# SparkFun_AVR_Stick.net
KiCad netlist of a schematic drawn in EAGLE
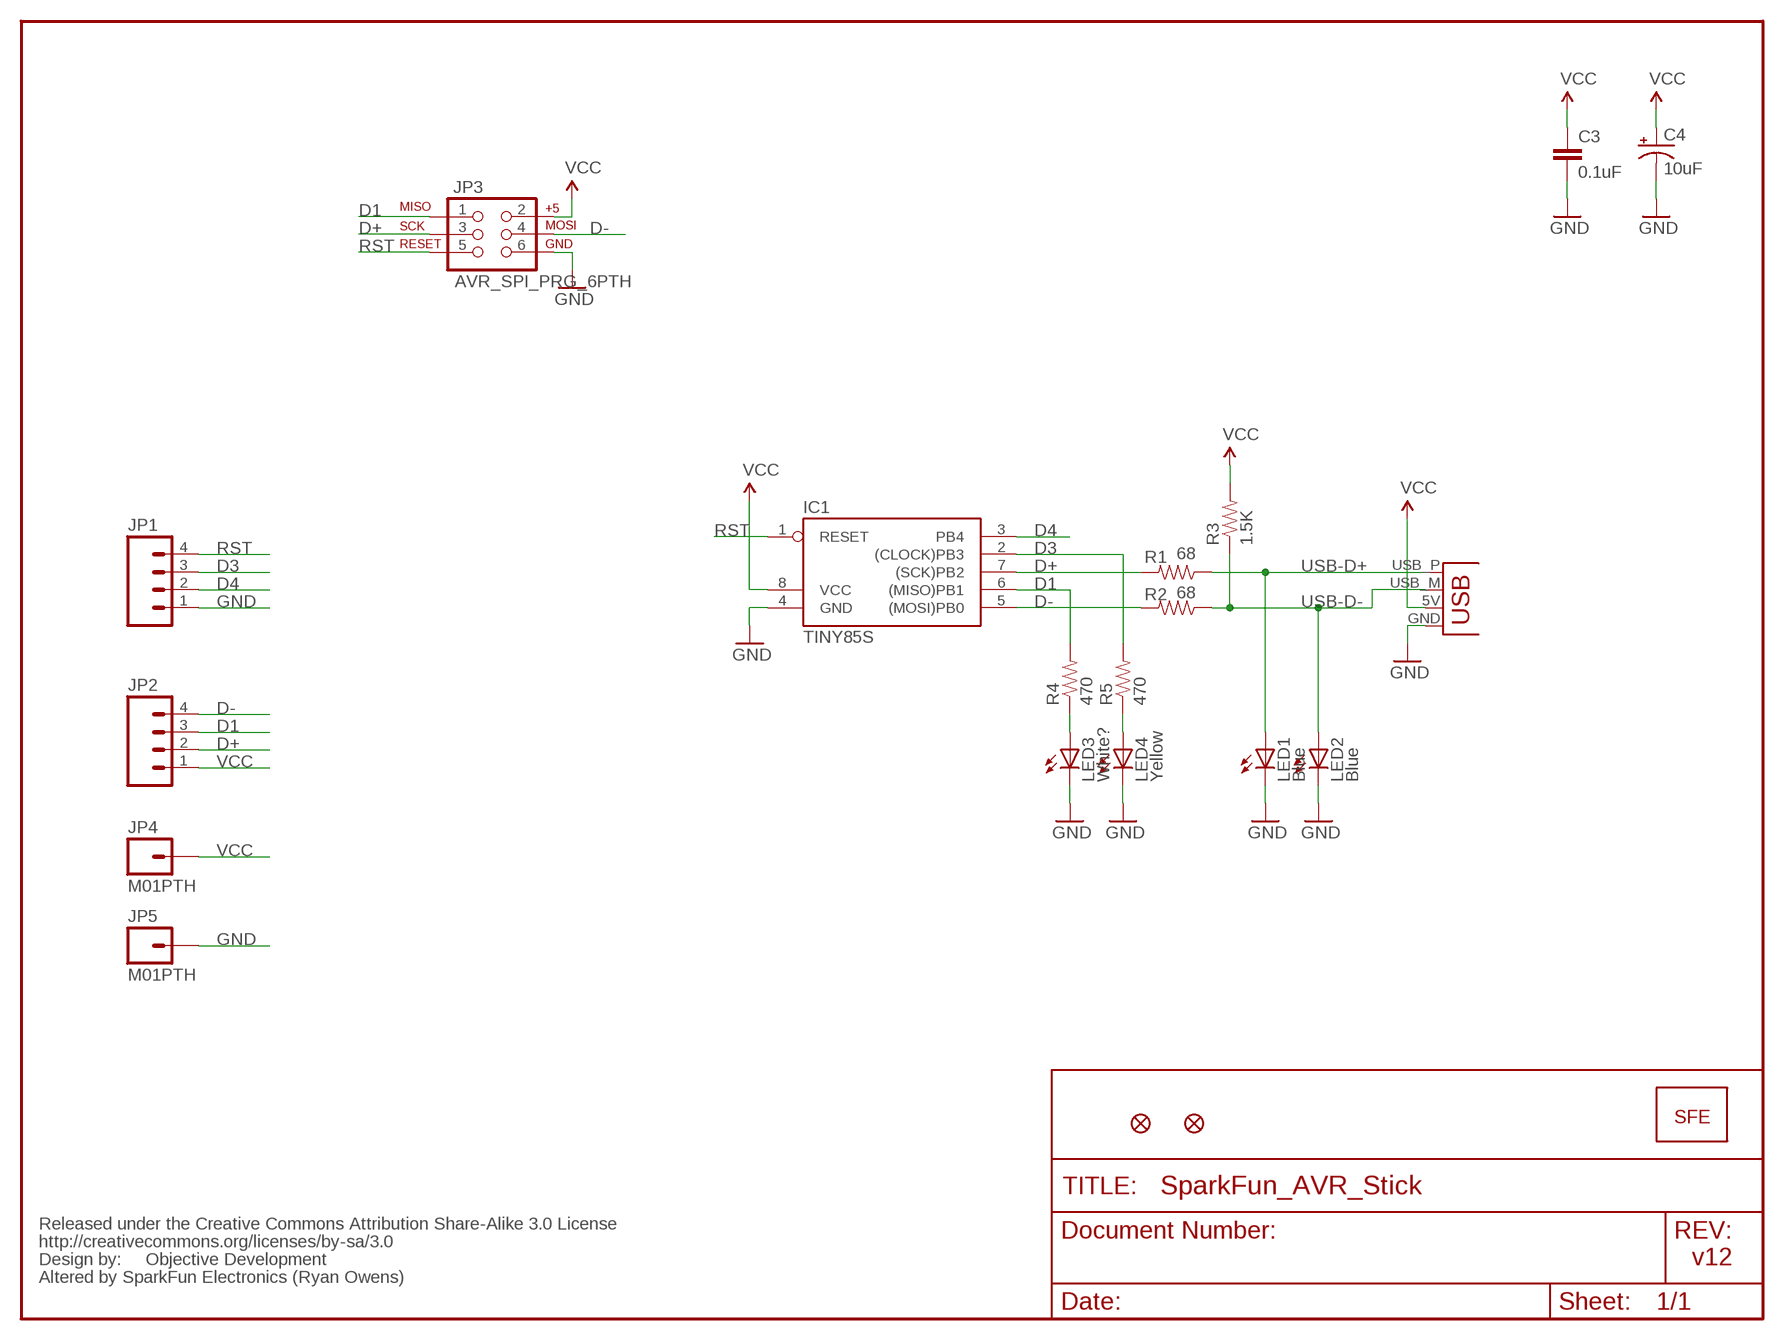
[diagram p0: schematic, sheet 1]

(export (version "E")
  (design (tool "Eeschema 10.0.6"))
  (components
    (comp (ref "C3")
      (value "0.1uF")
      (footprint "eagle-import:0402-CAP")
      (libsource (lib "eagle-import") (part "CAP0402-CAP"))
    )
    (comp (ref "C4")
      (value "10uF")
      (footprint "eagle-import:EIA3216")
      (libsource (lib "eagle-import") (part "CAP_POL1206"))
    )
    (comp (ref "IC1")
      (value "TINY85S")
      (footprint "eagle-import:SOIC8")
      (libsource (lib "eagle-import") (part "TINY85S"))
    )
    (comp (ref "JP1")
      (value "M04PTH")
      (footprint "eagle-import:1X04")
      (libsource (lib "eagle-import") (part "M04PTH"))
    )
    (comp (ref "JP2")
      (value "M04PTH")
      (footprint "eagle-import:1X04")
      (libsource (lib "eagle-import") (part "M04PTH"))
    )
    (comp (ref "JP3")
      (value "AVR_SPI_PRG_6PTH")
      (footprint "eagle-import:2X3")
      (libsource (lib "eagle-import") (part "AVR_SPI_PRG_6PTH"))
    )
    (comp (ref "JP4")
      (value "M01PTH")
      (footprint "eagle-import:1X01")
      (libsource (lib "eagle-import") (part "M01PTH"))
    )
    (comp (ref "JP5")
      (value "M01PTH")
      (footprint "eagle-import:1X01")
      (libsource (lib "eagle-import") (part "M01PTH"))
    )
    (comp (ref "LED1")
      (value "Blue")
      (footprint "eagle-import:LED-0603")
      (libsource (lib "eagle-import") (part "LED0603"))
    )
    (comp (ref "LED2")
      (value "Blue")
      (footprint "eagle-import:LED-0603")
      (libsource (lib "eagle-import") (part "LED0603"))
    )
    (comp (ref "LED3")
      (value "White?")
      (footprint "eagle-import:LED-0603")
      (libsource (lib "eagle-import") (part "LED0603"))
    )
    (comp (ref "LED4")
      (value "Yellow")
      (footprint "eagle-import:LED-0603")
      (libsource (lib "eagle-import") (part "LED0603"))
    )
    (comp (ref "R1")
      (value "68")
      (footprint "eagle-import:0402-RES")
      (libsource (lib "eagle-import") (part "RESISTOR0402-RES"))
    )
    (comp (ref "R2")
      (value "68")
      (footprint "eagle-import:0402-RES")
      (libsource (lib "eagle-import") (part "RESISTOR0402-RES"))
    )
    (comp (ref "R3")
      (value "1.5K")
      (footprint "eagle-import:0402-RES")
      (libsource (lib "eagle-import") (part "RESISTOR0402-RES"))
    )
    (comp (ref "R4")
      (value "470")
      (footprint "eagle-import:0402-RES")
      (libsource (lib "eagle-import") (part "RESISTOR0402-RES"))
    )
    (comp (ref "R5")
      (value "470")
      (footprint "eagle-import:0402-RES")
      (libsource (lib "eagle-import") (part "RESISTOR0402-RES"))
    )
    (comp (ref "U$1")
      (value "LOGO-SFESK")
      (footprint "eagle-import:SFE-LOGO-FLAME")
      (libsource (lib "eagle-import") (part "LOGO-SFESK"))
    )
    (comp (ref "U$2")
      (value "FIDUCIAL1X2")
      (footprint "eagle-import:FIDUCIAL-1X2")
      (libsource (lib "eagle-import") (part "FIDUCIAL1X2"))
    )
    (comp (ref "U$3")
      (value "FIDUCIAL1X2")
      (footprint "eagle-import:FIDUCIAL-1X2")
      (libsource (lib "eagle-import") (part "FIDUCIAL1X2"))
    )
    (comp (ref "U$4")
      (value "CREATIVE_COMMONS")
      (footprint "eagle-import:CREATIVE_COMMONS")
      (libsource (lib "eagle-import") (part "CREATIVE_COMMONS"))
    )
    (comp (ref "X1")
      (value "USBPCB")
      (footprint "eagle-import:USB-A-PCB")
      (libsource (lib "eagle-import") (part "USBPCB"))
    )
  )
  (nets
    (net (code "1") (name "/D+") (class "Default")
      (node (ref "IC1") (pin "7") (pinfunction "(SCK)PB2_7") (pintype "bidirectional"))
      (node (ref "JP2") (pin "2") (pinfunction "2_2") (pintype "passive"))
      (node (ref "JP3") (pin "3") (pinfunction "3_3") (pintype "passive"))
      (node (ref "R1") (pin "2") (pinfunction "2_2") (pintype "passive"))
    )
    (net (code "2") (name "/D-") (class "Default")
      (node (ref "IC1") (pin "5") (pinfunction "(MOSI)PB0_5") (pintype "bidirectional"))
      (node (ref "JP2") (pin "4") (pinfunction "4_4") (pintype "passive"))
      (node (ref "JP3") (pin "4") (pinfunction "4_4") (pintype "passive"))
      (node (ref "R2") (pin "2") (pinfunction "2_2") (pintype "passive"))
    )
    (net (code "3") (name "/D1") (class "Default")
      (node (ref "IC1") (pin "6") (pinfunction "(MISO)PB1_6") (pintype "bidirectional"))
      (node (ref "JP2") (pin "3") (pinfunction "3_3") (pintype "passive"))
      (node (ref "JP3") (pin "1") (pinfunction "1_1") (pintype "passive"))
      (node (ref "R4") (pin "2") (pinfunction "2_2") (pintype "passive"))
    )
    (net (code "4") (name "/D3") (class "Default")
      (node (ref "IC1") (pin "2") (pinfunction "(CLOCK)PB3_2") (pintype "bidirectional"))
      (node (ref "JP1") (pin "3") (pinfunction "3_3") (pintype "passive"))
      (node (ref "R5") (pin "2") (pinfunction "2_2") (pintype "passive"))
    )
    (net (code "5") (name "/D4") (class "Default")
      (node (ref "IC1") (pin "3") (pinfunction "PB4_3") (pintype "bidirectional"))
      (node (ref "JP1") (pin "2") (pinfunction "2_2") (pintype "passive"))
    )
    (net (code "6") (name "/RST") (class "Default")
      (node (ref "IC1") (pin "1") (pinfunction "RESET_1") (pintype "input"))
      (node (ref "JP1") (pin "4") (pinfunction "4_4") (pintype "passive"))
      (node (ref "JP3") (pin "5") (pinfunction "5_5") (pintype "passive"))
    )
    (net (code "7") (name "/USB-D+") (class "Default")
      (node (ref "LED1") (pin "A") (pinfunction "A_A") (pintype "passive"))
      (node (ref "R1") (pin "1") (pinfunction "1_1") (pintype "passive"))
      (node (ref "X1") (pin "USB_P") (pinfunction "D+_USB_P") (pintype "bidirectional"))
    )
    (net (code "8") (name "/USB-D-") (class "Default")
      (node (ref "LED2") (pin "A") (pinfunction "A_A") (pintype "passive"))
      (node (ref "R2") (pin "1") (pinfunction "1_1") (pintype "passive"))
      (node (ref "R3") (pin "1") (pinfunction "1_1") (pintype "passive"))
      (node (ref "X1") (pin "USB_M") (pinfunction "D-_USB_M") (pintype "bidirectional"))
    )
    (net (code "9") (name "GND") (class "Default")
      (node (ref "C3") (pin "2") (pinfunction "2_2") (pintype "passive"))
      (node (ref "C4") (pin "C") (pinfunction "-_C") (pintype "passive"))
      (node (ref "IC1") (pin "4") (pinfunction "GND_4") (pintype "power_in"))
      (node (ref "JP1") (pin "1") (pinfunction "1_1") (pintype "passive"))
      (node (ref "JP3") (pin "6") (pinfunction "6_6") (pintype "passive"))
      (node (ref "JP5") (pin "1") (pinfunction "1_1") (pintype "passive"))
      (node (ref "LED1") (pin "C") (pinfunction "C_C") (pintype "passive"))
      (node (ref "LED2") (pin "C") (pinfunction "C_C") (pintype "passive"))
      (node (ref "LED3") (pin "C") (pinfunction "C_C") (pintype "passive"))
      (node (ref "LED4") (pin "C") (pinfunction "C_C") (pintype "passive"))
      (node (ref "X1") (pin "GND") (pinfunction "GND_GND") (pintype "bidirectional"))
    )
    (net (code "10") (name "Net-(LED3-PadA)") (class "Default")
      (node (ref "LED3") (pin "A") (pinfunction "A_A") (pintype "passive"))
      (node (ref "R4") (pin "1") (pinfunction "1_1") (pintype "passive"))
    )
    (net (code "11") (name "Net-(LED4-PadA)") (class "Default")
      (node (ref "LED4") (pin "A") (pinfunction "A_A") (pintype "passive"))
      (node (ref "R5") (pin "1") (pinfunction "1_1") (pintype "passive"))
    )
    (net (code "12") (name "VCC") (class "Default")
      (node (ref "C3") (pin "1") (pinfunction "1_1") (pintype "passive"))
      (node (ref "C4") (pin "A") (pinfunction "+_A") (pintype "passive"))
      (node (ref "IC1") (pin "8") (pinfunction "VCC_8") (pintype "power_in"))
      (node (ref "JP2") (pin "1") (pinfunction "1_1") (pintype "passive"))
      (node (ref "JP3") (pin "2") (pinfunction "2_2") (pintype "passive"))
      (node (ref "JP4") (pin "1") (pinfunction "1_1") (pintype "passive"))
      (node (ref "R3") (pin "2") (pinfunction "2_2") (pintype "passive"))
      (node (ref "X1") (pin "5V") (pinfunction "VBUS_5V") (pintype "bidirectional"))
    )
  )
)
